# F-T-V_Converter_Schematic.net
KiCad netlist of a schematic drawn in Altium Designer
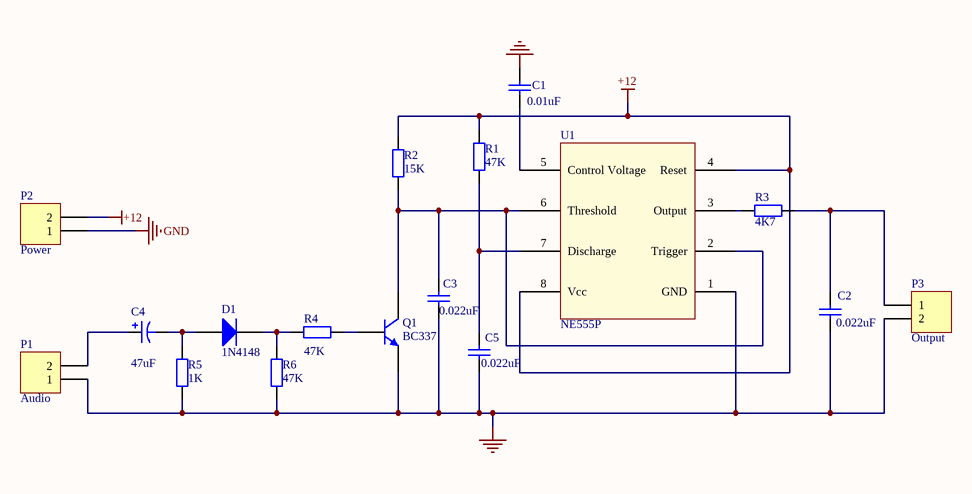
[diagram p0: F-T-V_Converter_Schematic.SchDoc]

(export (version "E")
  (design (tool "Eeschema 10.0.6"))
  (components
    (comp (ref "C1")
      (value "0.01uF")
      (footprint "RAD-0.1")
      (description "Capacitor: ceramic; MLCC, monolithic; 10nF; 100V; X7R; ±10%; THT")
      (fields
        (field (name "MANUFACTURER") "KEMET")
        (field (name "MANUFACTURER PART NUMBER") "C315C103K1R5TA")
        (field (name "PUBLISHER") "Altium Limited")
      )
      (libsource (lib "Miscellaneous Devices") (part "Cap"))
    )
    (comp (ref "C2")
      (value "0.022uF")
      (footprint "RAD-0.1")
      (description "Cap Ceramic 0.022uF 50V Z5U 20% Radial 5.08mm 85C T/R")
      (fields
        (field (name "MANUFACTURER") "KEMET")
        (field (name "MANUFACTURER PART NUMBER") "C317C223M5U5TA7301")
        (field (name "PUBLISHER") "Altium Limited")
      )
      (libsource (lib "Miscellaneous Devices") (part "Cap"))
    )
    (comp (ref "C3")
      (value "0.022uF")
      (footprint "RAD-0.1")
      (description "Cap Ceramic 0.022uF 50V Z5U 20% Radial 5.08mm 85C T/R")
      (fields
        (field (name "MANUFACTURER") "KEMET")
        (field (name "MANUFACTURER PART NUMBER") "C317C223M5U5TA7301")
        (field (name "PUBLISHER") "Altium Limited")
      )
      (libsource (lib "Miscellaneous Devices") (part "Cap"))
    )
    (comp (ref "C4")
      (value "47uF")
      (footprint "RB7.6-15")
      (description "Cap Aluminum 47uF 16V 20% Radial Aluminum Cylindrical Can 2mm 155mA 5000 hr 105°C Ammo Pack")
      (fields
        (field (name "MANUFACTURER") "Nichicon")
        (field (name "MANUFACTURER PART NUMBER") "UPV1C470MFD1TD")
        (field (name "PUBLISHER") "Altium Limited")
      )
      (libsource (lib "Miscellaneous Devices") (part "Cap Pol1"))
    )
    (comp (ref "C5")
      (value "0.022uF")
      (footprint "RAD-0.1")
      (description "Cap Ceramic 0.022uF 50V Z5U 20% Radial 5.08mm 85C T/R")
      (fields
        (field (name "MANUFACTURER") "KEMET")
        (field (name "MANUFACTURER PART NUMBER") "C317C223M5U5TA7301")
        (field (name "PUBLISHER") "Altium Limited")
      )
      (libsource (lib "Miscellaneous Devices") (part "Cap"))
    )
    (comp (ref "D1")
      (value "1N4148")
      (footprint "DO-35")
      (description "High Conductance Fast Diode")
      (fields (field (name "PUBLISHER") "Altium Limited"))
      (libsource (lib "Miscellaneous Devices") (part "Diode 1N4148"))
    )
    (comp (ref "P1")
      (value "Audio")
      (footprint "HDR1X2")
      (description "Header, 2-Pin")
      (fields (field (name "PUBLISHER") "Altium Limited"))
      (libsource (lib "") (part "Header 2_1"))
    )
    (comp (ref "P2")
      (value "Power")
      (footprint "HDR1X2")
      (description "Header, 2-Pin")
      (fields (field (name "PUBLISHER") "Altium Limited"))
      (libsource (lib "") (part "Header 2_1"))
    )
    (comp (ref "P3")
      (value "Output")
      (footprint "HDR1X2")
      (description "Header, 2-Pin")
      (fields (field (name "PUBLISHER") "Altium Limited"))
      (libsource (lib "Miscellaneous Connectors") (part "Header 2"))
    )
    (comp (ref "Q1")
      (value "BC337")
      (footprint "TO-92")
      (description "NPN Bipolar Transistor")
      (fields (field (name "PUBLISHER") "Altium Limited"))
      (libsource (lib "Miscellaneous Devices") (part "NPN"))
    )
    (comp (ref "R1")
      (value "47K")
      (footprint "AXIAL-0.4")
      (description "Resistor")
      (fields (field (name "Comment") "Res2") (field (name "PUBLISHER") "Altium Limited"))
      (libsource (lib "Miscellaneous Devices") (part "Res2"))
    )
    (comp (ref "R2")
      (value "15K")
      (footprint "AXIAL-0.4")
      (description "Resistor")
      (fields (field (name "Comment") "Res2") (field (name "PUBLISHER") "Altium Limited"))
      (libsource (lib "Miscellaneous Devices") (part "Res2"))
    )
    (comp (ref "R3")
      (value "4K7")
      (footprint "AXIAL-0.4")
      (description "RES 4.7K OHM 1/4W 5% AXIAL")
      (fields
        (field (name "MANUFACTURER") "Stackpole Electronics")
        (field (name "MANUFACTURER PART NUMBER") "CF14JT47K0")
        (field (name "PUBLISHER") "Altium Limited")
      )
      (libsource (lib "") (part "Res2_1"))
    )
    (comp (ref "R4")
      (value "47K")
      (footprint "AXIAL-0.4")
      (description "Resistor")
      (fields (field (name "Comment") "Res2") (field (name "PUBLISHER") "Altium Limited"))
      (libsource (lib "") (part "Res2_1"))
    )
    (comp (ref "R5")
      (value "1K")
      (footprint "AXIAL-0.4")
      (description "Resistor")
      (fields (field (name "PUBLISHER") "Altium Limited"))
      (libsource (lib "Miscellaneous Devices") (part "Res2"))
    )
    (comp (ref "R6")
      (value "47K")
      (footprint "AXIAL-0.4")
      (description "Resistor")
      (fields (field (name "Comment") "Res2") (field (name "PUBLISHER") "Altium Limited"))
      (libsource (lib "Miscellaneous Devices") (part "Res2"))
    )
    (comp (ref "U1")
      (value "NE555P")
      (footprint "NE555")
      (description "Standard Timer Single 8-Pin PDIP Tube")
      (fields (field (name "MANUFACTURER") "Texas Instruments"))
      (libsource (lib "IC_Timers") (part "NE555P"))
    )
  )
  (nets
    (net (code "1") (name "+12") (class "Default")
      (node (ref "P2") (pin "2") (pinfunction "2_2") (pintype "passive"))
      (node (ref "R1") (pin "2") (pinfunction "2_2") (pintype "passive"))
      (node (ref "R2") (pin "2") (pinfunction "2_2") (pintype "passive"))
      (node (ref "U1") (pin "4") (pinfunction "Reset_4") (pintype "passive"))
      (node (ref "U1") (pin "8") (pinfunction "Vcc_8") (pintype "passive"))
    )
    (net (code "2") (name "GND") (class "Default")
      (node (ref "C1") (pin "2") (pinfunction "2_2") (pintype "passive"))
      (node (ref "C2") (pin "1") (pinfunction "1_1") (pintype "passive"))
      (node (ref "C3") (pin "1") (pinfunction "1_1") (pintype "passive"))
      (node (ref "C5") (pin "1") (pinfunction "1_1") (pintype "passive"))
      (node (ref "P1") (pin "1") (pinfunction "1_1") (pintype "passive"))
      (node (ref "P2") (pin "1") (pinfunction "1_1") (pintype "passive"))
      (node (ref "P3") (pin "2") (pinfunction "2_2") (pintype "passive"))
      (node (ref "Q1") (pin "3") (pinfunction "E_3") (pintype "passive"))
      (node (ref "R5") (pin "1") (pinfunction "1_1") (pintype "passive"))
      (node (ref "R6") (pin "1") (pinfunction "1_1") (pintype "passive"))
      (node (ref "U1") (pin "1") (pinfunction "GND_1") (pintype "passive"))
    )
    (net (code "3") (name "Net-(C2-Pad2)") (class "Default")
      (node (ref "C2") (pin "2") (pinfunction "2_2") (pintype "passive"))
      (node (ref "P3") (pin "1") (pinfunction "1_1") (pintype "passive"))
      (node (ref "R3") (pin "2") (pinfunction "2_2") (pintype "passive"))
    )
    (net (code "4") (name "Net-(C4-Pad1)") (class "Default")
      (node (ref "C4") (pin "1") (pinfunction "1_1") (pintype "passive"))
      (node (ref "P1") (pin "2") (pinfunction "2_2") (pintype "passive"))
    )
    (net (code "5") (name "Net-(D1-A)") (class "Default")
      (node (ref "C4") (pin "2") (pinfunction "2_2") (pintype "passive"))
      (node (ref "D1") (pin "1") (pinfunction "A_1") (pintype "passive"))
      (node (ref "R5") (pin "2") (pinfunction "2_2") (pintype "passive"))
    )
    (net (code "6") (name "Net-(D1-K)") (class "Default")
      (node (ref "D1") (pin "2") (pinfunction "K_2") (pintype "passive"))
      (node (ref "R4") (pin "1") (pinfunction "1_1") (pintype "passive"))
      (node (ref "R6") (pin "2") (pinfunction "2_2") (pintype "passive"))
    )
    (net (code "7") (name "Net-(Q1-B)") (class "Default")
      (node (ref "Q1") (pin "2") (pinfunction "B_2") (pintype "passive"))
      (node (ref "R4") (pin "2") (pinfunction "2_2") (pintype "passive"))
    )
    (net (code "8") (name "Net-(Q1-C)") (class "Default")
      (node (ref "C3") (pin "2") (pinfunction "2_2") (pintype "passive"))
      (node (ref "Q1") (pin "1") (pinfunction "C_1") (pintype "passive"))
      (node (ref "R2") (pin "1") (pinfunction "1_1") (pintype "passive"))
      (node (ref "U1") (pin "2") (pinfunction "Trigger_2") (pintype "passive"))
      (node (ref "U1") (pin "6") (pinfunction "Threshold_6") (pintype "passive"))
    )
    (net (code "9") (name "Net-(U1-Control_Voltage)") (class "Default")
      (node (ref "C1") (pin "1") (pinfunction "1_1") (pintype "passive"))
      (node (ref "U1") (pin "5") (pinfunction "Control_Voltage_5") (pintype "passive"))
    )
    (net (code "10") (name "Net-(U1-Discharge)") (class "Default")
      (node (ref "C5") (pin "2") (pinfunction "2_2") (pintype "passive"))
      (node (ref "R1") (pin "1") (pinfunction "1_1") (pintype "passive"))
      (node (ref "U1") (pin "7") (pinfunction "Discharge_7") (pintype "passive"))
    )
    (net (code "11") (name "Net-(U1-Output)") (class "Default")
      (node (ref "R3") (pin "1") (pinfunction "1_1") (pintype "passive"))
      (node (ref "U1") (pin "3") (pinfunction "Output_3") (pintype "passive"))
    )
  )
)
